# MCU.net
KiCad netlist of a schematic drawn in Altium Designer
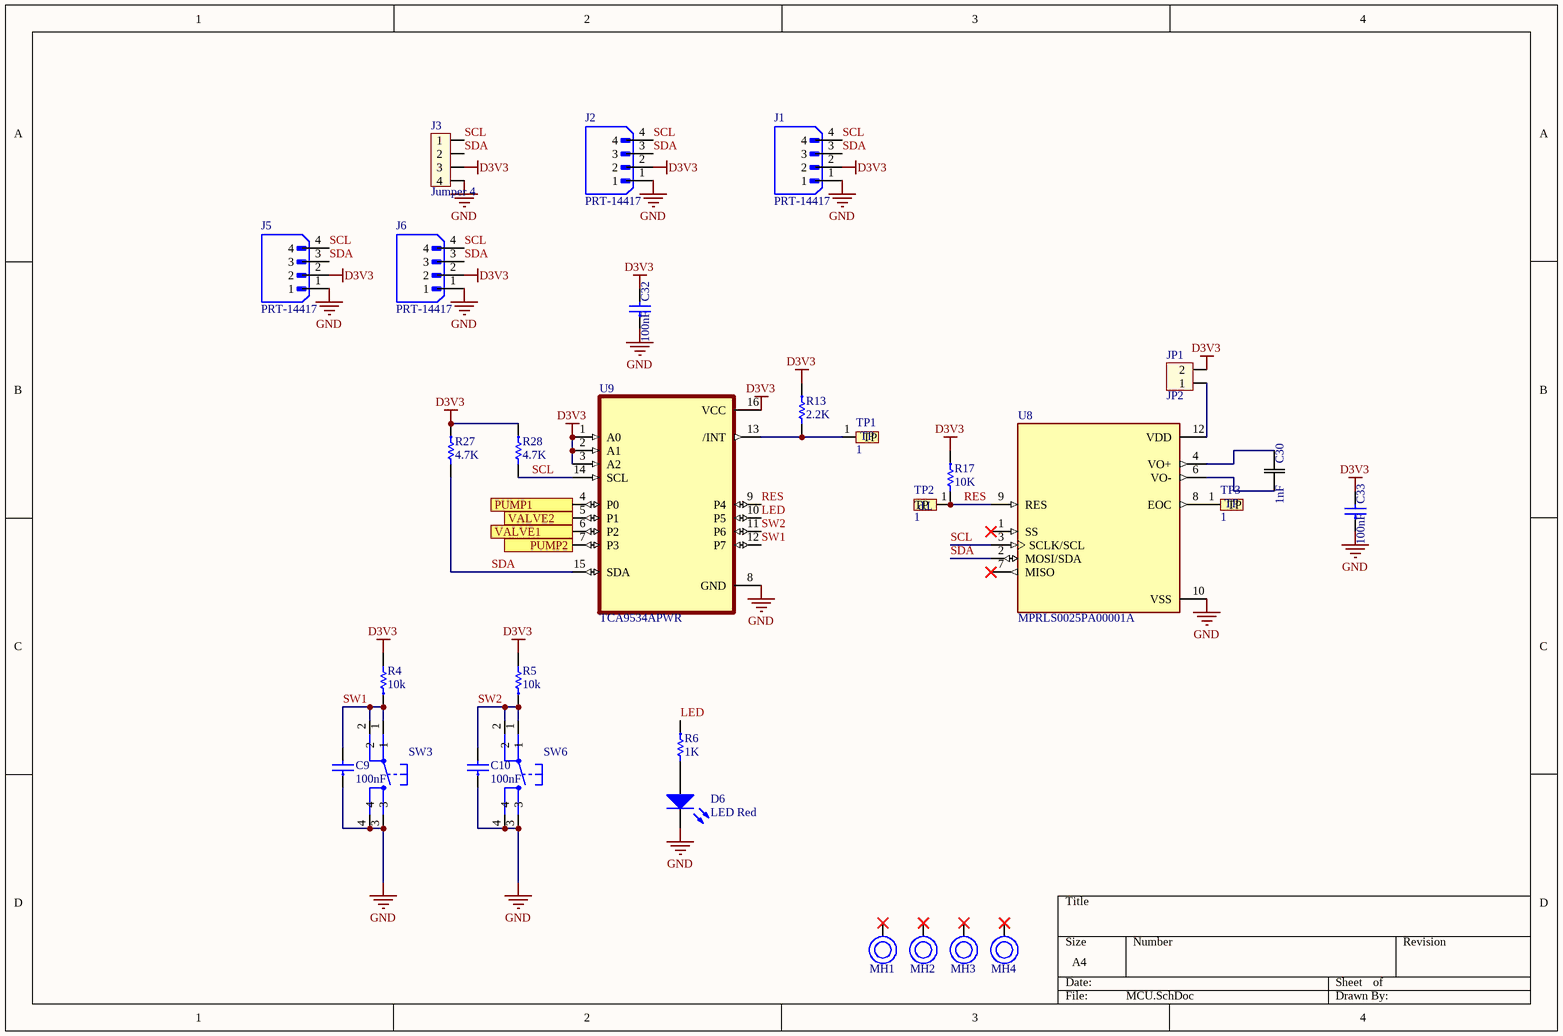
[diagram p0: MCU.SchDoc]

(export (version "E")
  (design (tool "Eeschema 10.0.6"))
  (components
    (comp (ref "C9")
      (value "100nF")
      (footprint "C0603")
      (description "CAP CER 100nF 10% 50V X7R 0603 SMD")
      (libsource (lib "2502-GMQLITE-MAIN") (part "CAPCER0001 100nF 10% 50V X7R 0603 SMD"))
    )
    (comp (ref "C10")
      (value "100nF")
      (footprint "C0603")
      (description "CAP CER 100nF 10% 50V X7R 0603 SMD")
      (libsource (lib "2502-GMQLITE-MAIN") (part "CAPCER0001 100nF 10% 50V X7R 0603 SMD"))
    )
    (comp (ref "C30")
      (value "1nF")
      (footprint "CAP_GCJ18_1p8X0p9X0p9_MUR")
      (description "No Description Available")
      (fields
        (field (name "MANUFACTURER_PART_NUMBER") "GCJ188R71H102KA01D")
        (field (name "COPYRIGHT") "Copyright (C) 2026 Ultra Librarian. All rights reserved.")
      )
      (libsource (lib "GCJ188R71H102KA01D") (part "GCJ188R71H102KA01D"))
    )
    (comp (ref "C32")
      (value "100nF")
      (footprint "C0603")
      (description "CAP CER 100nF 10% 50V X7R 0603 SMD")
      (libsource (lib "2502-GMQLITE-MAIN") (part "CAPCER0001 100nF 10% 50V X7R 0603 SMD"))
    )
    (comp (ref "C33")
      (value "100nF")
      (footprint "CL10A106MQ8NNNC:C0603")
      (description "CAP CER 100nF 10% 50V X7R 0603 SMD")
      (libsource (lib "2502-GMQLITE-MAIN") (part "CAPCER0001 100nF 10% 50V X7R 0603 SMD"))
    )
    (comp (ref "D6")
      (value "LED Red")
      (footprint "LED0603-R")
      (description "Lite-On LED Red 0603")
      (libsource (lib "diode") (part "LTST-C190KRKT"))
    )
    (comp (ref "J1")
      (value "PRT-14417")
      (footprint "SPARKFUN_PRT-14417")
      (description "QWIIC JST CONNECTOR - SMD 4-PIN")
      (fields (field (name "MF") "SparkFun Electronics"))
      (libsource (lib "PRT-14417") (part "PRT-14417"))
    )
    (comp (ref "J2")
      (value "PRT-14417")
      (footprint "SPARKFUN_PRT-14417")
      (description "QWIIC JST CONNECTOR - SMD 4-PIN")
      (fields (field (name "MF") "SparkFun Electronics"))
      (libsource (lib "PRT-14417") (part "PRT-14417"))
    )
    (comp (ref "J3")
      (value "Jumper 4")
      (footprint "JP4")
      (description "Jumper 3")
      (libsource (lib "hanguyen") (part "JP4"))
    )
    (comp (ref "J5")
      (value "PRT-14417")
      (footprint "SPARKFUN_PRT-14417")
      (description "QWIIC JST CONNECTOR - SMD 4-PIN")
      (fields (field (name "MF") "SparkFun Electronics"))
      (libsource (lib "PRT-14417") (part "PRT-14417"))
    )
    (comp (ref "J6")
      (value "PRT-14417")
      (footprint "SPARKFUN_PRT-14417")
      (description "QWIIC JST CONNECTOR - SMD 4-PIN")
      (fields (field (name "MF") "SparkFun Electronics"))
      (libsource (lib "PRT-14417") (part "PRT-14417"))
    )
    (comp (ref "JP1")
      (value "JP2")
      (footprint "JP2-CLOSED")
      (description "jumper 2.0 B")
      (libsource (lib "hanguyen") (part "Con2"))
    )
    (comp (ref "MH1") (value "MOUNTING HOLE") (footprint "M3") (libsource (lib "INVERTER") (part "MH")))
    (comp (ref "MH2") (value "MOUNTING HOLE") (footprint "M3") (libsource (lib "INVERTER") (part "MH")))
    (comp (ref "MH3") (value "MOUNTING HOLE") (footprint "M3") (libsource (lib "INVERTER") (part "MH")))
    (comp (ref "MH4") (value "MOUNTING HOLE") (footprint "M3") (libsource (lib "INVERTER") (part "MH")))
    (comp (ref "R4")
      (value "10k")
      (footprint "R0603")
      (description "RES CHP 8K4 1% 1/10W 0603 SMD")
      (libsource (lib "2502-GMQLITE-MAIN") (part "RESCHP0428 8K4 1% 0603 SMD"))
    )
    (comp (ref "R5")
      (value "10k")
      (footprint "R0603")
      (description "RES CHP 8K4 1% 1/10W 0603 SMD")
      (libsource (lib "2502-GMQLITE-MAIN") (part "RESCHP0428 8K4 1% 0603 SMD"))
    )
    (comp (ref "R6")
      (value "1K")
      (footprint "R0603")
      (description "RES CHP 8K4 1% 1/10W 0603 SMD")
      (libsource (lib "2502-GMQLITE-MAIN") (part "RESCHP0428 8K4 1% 0603 SMD"))
    )
    (comp (ref "R13")
      (value "2.2K")
      (footprint "R0603")
      (description "RES CHP 8K4 1% 1/10W 0603 SMD")
      (libsource (lib "2502-GMQLITE-MAIN") (part "RESCHP0428 8K4 1% 0603 SMD"))
    )
    (comp (ref "R17")
      (value "10K")
      (footprint "R0603")
      (description "RES CHP 8K4 1% 1/10W 0603 SMD")
      (libsource (lib "2502-GMQLITE-MAIN") (part "RESCHP0428 8K4 1% 0603 SMD"))
    )
    (comp (ref "R27")
      (value "4.7K")
      (footprint "R0603")
      (description "RES CHP 8K4 1% 1/10W 0603 SMD")
      (libsource (lib "2502-GMQLITE-MAIN") (part "RESCHP0428 8K4 1% 0603 SMD"))
    )
    (comp (ref "R28")
      (value "4.7K")
      (footprint "R0603")
      (description "RES CHP 8K4 1% 1/10W 0603 SMD")
      (libsource (lib "2502-GMQLITE-MAIN") (part "RESCHP0428 8K4 1% 0603 SMD"))
    )
    (comp (ref "SW3")
      (value "SW2")
      (footprint "SWITCH")
      (description "Switch button 4 pin")
      (libsource (lib "Stm32_Flyback_Driver_250814_1") (part "SW2"))
    )
    (comp (ref "SW6")
      (value "SW2")
      (footprint "SWITCH")
      (description "Switch button 4 pin")
      (libsource (lib "Stm32_Flyback_Driver_250814_1") (part "SW2"))
    )
    (comp (ref "TP1")
      (value "1")
      (footprint "TP")
      (description "CONNECT 1")
      (libsource (lib "") (part "TP_1"))
    )
    (comp (ref "TP2")
      (value "1")
      (footprint "TP")
      (description "CONNECT 1")
      (libsource (lib "hanguyen") (part "TP"))
    )
    (comp (ref "TP3")
      (value "1")
      (footprint "TP")
      (description "CONNECT 1")
      (libsource (lib "") (part "TP_1"))
    )
    (comp (ref "U8")
      (value "MPRLS0025PA00001A")
      (footprint "SnapEDApcb:XDCR_MPRLS0025PA00001A")
      (description "Pressure Sensor 25PSI _172.37kPa_ Absolute Male - 0.1 _2.5mm_ Tube 24 b 12-SMD Module")
      (fields (field (name "DIGI-KEY_PART_NUMBER") "480-7098-1-ND") (field (name "MF") "Honeywell Sensing"))
      (libsource (lib "SnapEDAsch") (part "MPRLS0025PA00001A"))
    )
    (comp (ref "U9")
      (value "TCA9534APWR")
      (footprint "SOP65P640X120-16N")
      (description "8-bit 1.65- to 5.5-V I2C/SMBus I/O expander with interrupt, & config registers")
      (fields (field (name "MF") "Texas Instruments"))
      (libsource (lib "TCA9534APWR") (part "TCA9534APWR"))
    )
  )
  (nets
    (net (code "1") (name "/LED") (class "Default")
      (node (ref "R6") (pin "1") (pinfunction "1_1") (pintype "passive"))
      (node (ref "U9") (pin "10") (pinfunction "P5_10") (pintype "bidirectional"))
    )
    (net (code "2") (name "/PUMP1") (class "Default")
      (node (ref "U9") (pin "4") (pinfunction "P0_4") (pintype "bidirectional"))
    )
    (net (code "3") (name "/PUMP2") (class "Default")
      (node (ref "U9") (pin "7") (pinfunction "P3_7") (pintype "bidirectional"))
    )
    (net (code "4") (name "/RES") (class "Default")
      (node (ref "R17") (pin "2") (pinfunction "2_2") (pintype "passive"))
      (node (ref "TP2") (pin "1") (pinfunction "TP_1") (pintype "passive"))
      (node (ref "U8") (pin "9") (pinfunction "RES_9") (pintype "input"))
      (node (ref "U9") (pin "9") (pinfunction "P4_9") (pintype "bidirectional"))
    )
    (net (code "5") (name "/SCL") (class "Default")
      (node (ref "J1") (pin "4") (pinfunction "4_4") (pintype "passive"))
      (node (ref "J2") (pin "4") (pinfunction "4_4") (pintype "passive"))
      (node (ref "J3") (pin "1") (pinfunction "1_1") (pintype "passive"))
      (node (ref "J5") (pin "4") (pinfunction "4_4") (pintype "passive"))
      (node (ref "J6") (pin "4") (pinfunction "4_4") (pintype "passive"))
      (node (ref "R28") (pin "2") (pinfunction "2_2") (pintype "passive"))
      (node (ref "U8") (pin "3") (pinfunction "SCLK/SCL_3") (pintype "input"))
      (node (ref "U9") (pin "14") (pinfunction "SCL_14") (pintype "input"))
    )
    (net (code "6") (name "/SDA") (class "Default")
      (node (ref "J1") (pin "3") (pinfunction "3_3") (pintype "passive"))
      (node (ref "J2") (pin "3") (pinfunction "3_3") (pintype "passive"))
      (node (ref "J3") (pin "2") (pinfunction "2_2") (pintype "passive"))
      (node (ref "J5") (pin "3") (pinfunction "3_3") (pintype "passive"))
      (node (ref "J6") (pin "3") (pinfunction "3_3") (pintype "passive"))
      (node (ref "R27") (pin "2") (pinfunction "2_2") (pintype "passive"))
      (node (ref "U8") (pin "2") (pinfunction "MOSI/SDA_2") (pintype "bidirectional"))
      (node (ref "U9") (pin "15") (pinfunction "SDA_15") (pintype "bidirectional"))
    )
    (net (code "7") (name "/SW1") (class "Default")
      (node (ref "C9") (pin "2") (pinfunction "2_2") (pintype "passive"))
      (node (ref "R4") (pin "1") (pinfunction "1_1") (pintype "passive"))
      (node (ref "SW3") (pin "1") (pinfunction "1_1") (pintype "passive"))
      (node (ref "SW3") (pin "2") (pinfunction "2_2") (pintype "passive"))
      (node (ref "U9") (pin "12") (pinfunction "P7_12") (pintype "bidirectional"))
    )
    (net (code "8") (name "/SW2") (class "Default")
      (node (ref "C10") (pin "2") (pinfunction "2_2") (pintype "passive"))
      (node (ref "R5") (pin "1") (pinfunction "1_1") (pintype "passive"))
      (node (ref "SW6") (pin "1") (pinfunction "1_1") (pintype "passive"))
      (node (ref "SW6") (pin "2") (pinfunction "2_2") (pintype "passive"))
      (node (ref "U9") (pin "11") (pinfunction "P6_11") (pintype "bidirectional"))
    )
    (net (code "9") (name "/VALVE1") (class "Default")
      (node (ref "U9") (pin "6") (pinfunction "P2_6") (pintype "bidirectional"))
    )
    (net (code "10") (name "/VALVE2") (class "Default")
      (node (ref "U9") (pin "5") (pinfunction "P1_5") (pintype "bidirectional"))
    )
    (net (code "11") (name "D3V3") (class "Default")
      (node (ref "C32") (pin "2") (pinfunction "2_2") (pintype "passive"))
      (node (ref "C33") (pin "2") (pinfunction "2_2") (pintype "passive"))
      (node (ref "J1") (pin "2") (pinfunction "2_2") (pintype "passive"))
      (node (ref "J2") (pin "2") (pinfunction "2_2") (pintype "passive"))
      (node (ref "J3") (pin "3") (pinfunction "3_3") (pintype "passive"))
      (node (ref "J5") (pin "2") (pinfunction "2_2") (pintype "passive"))
      (node (ref "J6") (pin "2") (pinfunction "2_2") (pintype "passive"))
      (node (ref "JP1") (pin "2") (pinfunction "2_2") (pintype "passive"))
      (node (ref "R13") (pin "1") (pinfunction "1_1") (pintype "passive"))
      (node (ref "R17") (pin "1") (pinfunction "1_1") (pintype "passive"))
      (node (ref "R27") (pin "1") (pinfunction "1_1") (pintype "passive"))
      (node (ref "R28") (pin "1") (pinfunction "1_1") (pintype "passive"))
      (node (ref "R4") (pin "2") (pinfunction "2_2") (pintype "passive"))
      (node (ref "R5") (pin "2") (pinfunction "2_2") (pintype "passive"))
      (node (ref "U9") (pin "1") (pinfunction "A0_1") (pintype "input"))
      (node (ref "U9") (pin "16") (pinfunction "VCC_16") (pintype "power_in"))
      (node (ref "U9") (pin "2") (pinfunction "A1_2") (pintype "input"))
      (node (ref "U9") (pin "3") (pinfunction "A2_3") (pintype "input"))
    )
    (net (code "12") (name "GND") (class "Default")
      (node (ref "C10") (pin "1") (pinfunction "1_1") (pintype "passive"))
      (node (ref "C32") (pin "1") (pinfunction "1_1") (pintype "passive"))
      (node (ref "C33") (pin "1") (pinfunction "1_1") (pintype "passive"))
      (node (ref "C9") (pin "1") (pinfunction "1_1") (pintype "passive"))
      (node (ref "D6") (pin "2") (pinfunction "K_2") (pintype "passive"))
      (node (ref "J1") (pin "1") (pinfunction "1_1") (pintype "passive"))
      (node (ref "J2") (pin "1") (pinfunction "1_1") (pintype "passive"))
      (node (ref "J3") (pin "4") (pinfunction "4_4") (pintype "passive"))
      (node (ref "J5") (pin "1") (pinfunction "1_1") (pintype "passive"))
      (node (ref "J6") (pin "1") (pinfunction "1_1") (pintype "passive"))
      (node (ref "SW3") (pin "3") (pinfunction "3_3") (pintype "passive"))
      (node (ref "SW3") (pin "4") (pinfunction "4_4") (pintype "passive"))
      (node (ref "SW6") (pin "3") (pinfunction "3_3") (pintype "passive"))
      (node (ref "SW6") (pin "4") (pinfunction "4_4") (pintype "passive"))
      (node (ref "U8") (pin "10") (pinfunction "VSS_10") (pintype "power_in"))
      (node (ref "U9") (pin "8") (pinfunction "GND_8") (pintype "power_in"))
    )
    (net (code "13") (name "Net-(D6-A)") (class "Default")
      (node (ref "D6") (pin "1") (pinfunction "A_1") (pintype "passive"))
      (node (ref "R6") (pin "2") (pinfunction "2_2") (pintype "passive"))
    )
    (net (code "14") (name "Net-(TP1-TP)") (class "Default")
      (node (ref "R13") (pin "2") (pinfunction "2_2") (pintype "passive"))
      (node (ref "TP1") (pin "1") (pinfunction "TP_1") (pintype "passive"))
      (node (ref "U9") (pin "13") (pinfunction "/INT_13") (pintype "output"))
    )
    (net (code "15") (name "Net-(TP3-TP)") (class "Default")
      (node (ref "TP3") (pin "1") (pinfunction "TP_1") (pintype "passive"))
      (node (ref "U8") (pin "8") (pinfunction "EOC_8") (pintype "output"))
    )
    (net (code "16") (name "Net-(U8-VDD)") (class "Default")
      (node (ref "JP1") (pin "1") (pinfunction "1_1") (pintype "passive"))
      (node (ref "U8") (pin "12") (pinfunction "VDD_12") (pintype "power_in"))
    )
    (net (code "17") (name "Net-(U8-VO+)") (class "Default")
      (node (ref "C30") (pin "2") (pinfunction "2_2") (pintype "passive"))
      (node (ref "U8") (pin "4") (pinfunction "VO+_4") (pintype "output"))
    )
    (net (code "18") (name "Net-(U8-VO-)") (class "Default")
      (node (ref "C30") (pin "1") (pinfunction "1_1") (pintype "passive"))
      (node (ref "U8") (pin "6") (pinfunction "VO-_6") (pintype "output"))
    )
    (net (code "19") (name "unconnected-(MH1-GND-Pad1)") (class "Default")
      (node (ref "MH1") (pin "1") (pinfunction "GND_1") (pintype "passive+no_connect"))
    )
    (net (code "20") (name "unconnected-(MH2-GND-Pad1)") (class "Default")
      (node (ref "MH2") (pin "1") (pinfunction "GND_1") (pintype "passive+no_connect"))
    )
    (net (code "21") (name "unconnected-(MH3-GND-Pad1)") (class "Default")
      (node (ref "MH3") (pin "1") (pinfunction "GND_1") (pintype "passive+no_connect"))
    )
    (net (code "22") (name "unconnected-(MH4-GND-Pad1)") (class "Default")
      (node (ref "MH4") (pin "1") (pinfunction "GND_1") (pintype "passive+no_connect"))
    )
    (net (code "23") (name "unconnected-(U8-MISO-Pad7)") (class "Default")
      (node (ref "U8") (pin "7") (pinfunction "MISO_7") (pintype "output+no_connect"))
    )
    (net (code "24") (name "unconnected-(U8-SS-Pad1)") (class "Default")
      (node (ref "U8") (pin "1") (pinfunction "SS_1") (pintype "input+no_connect"))
    )
  )
)
